# Rigid-Flex_HDMI_Switch.net
KiCad netlist of a schematic drawn in EAGLE
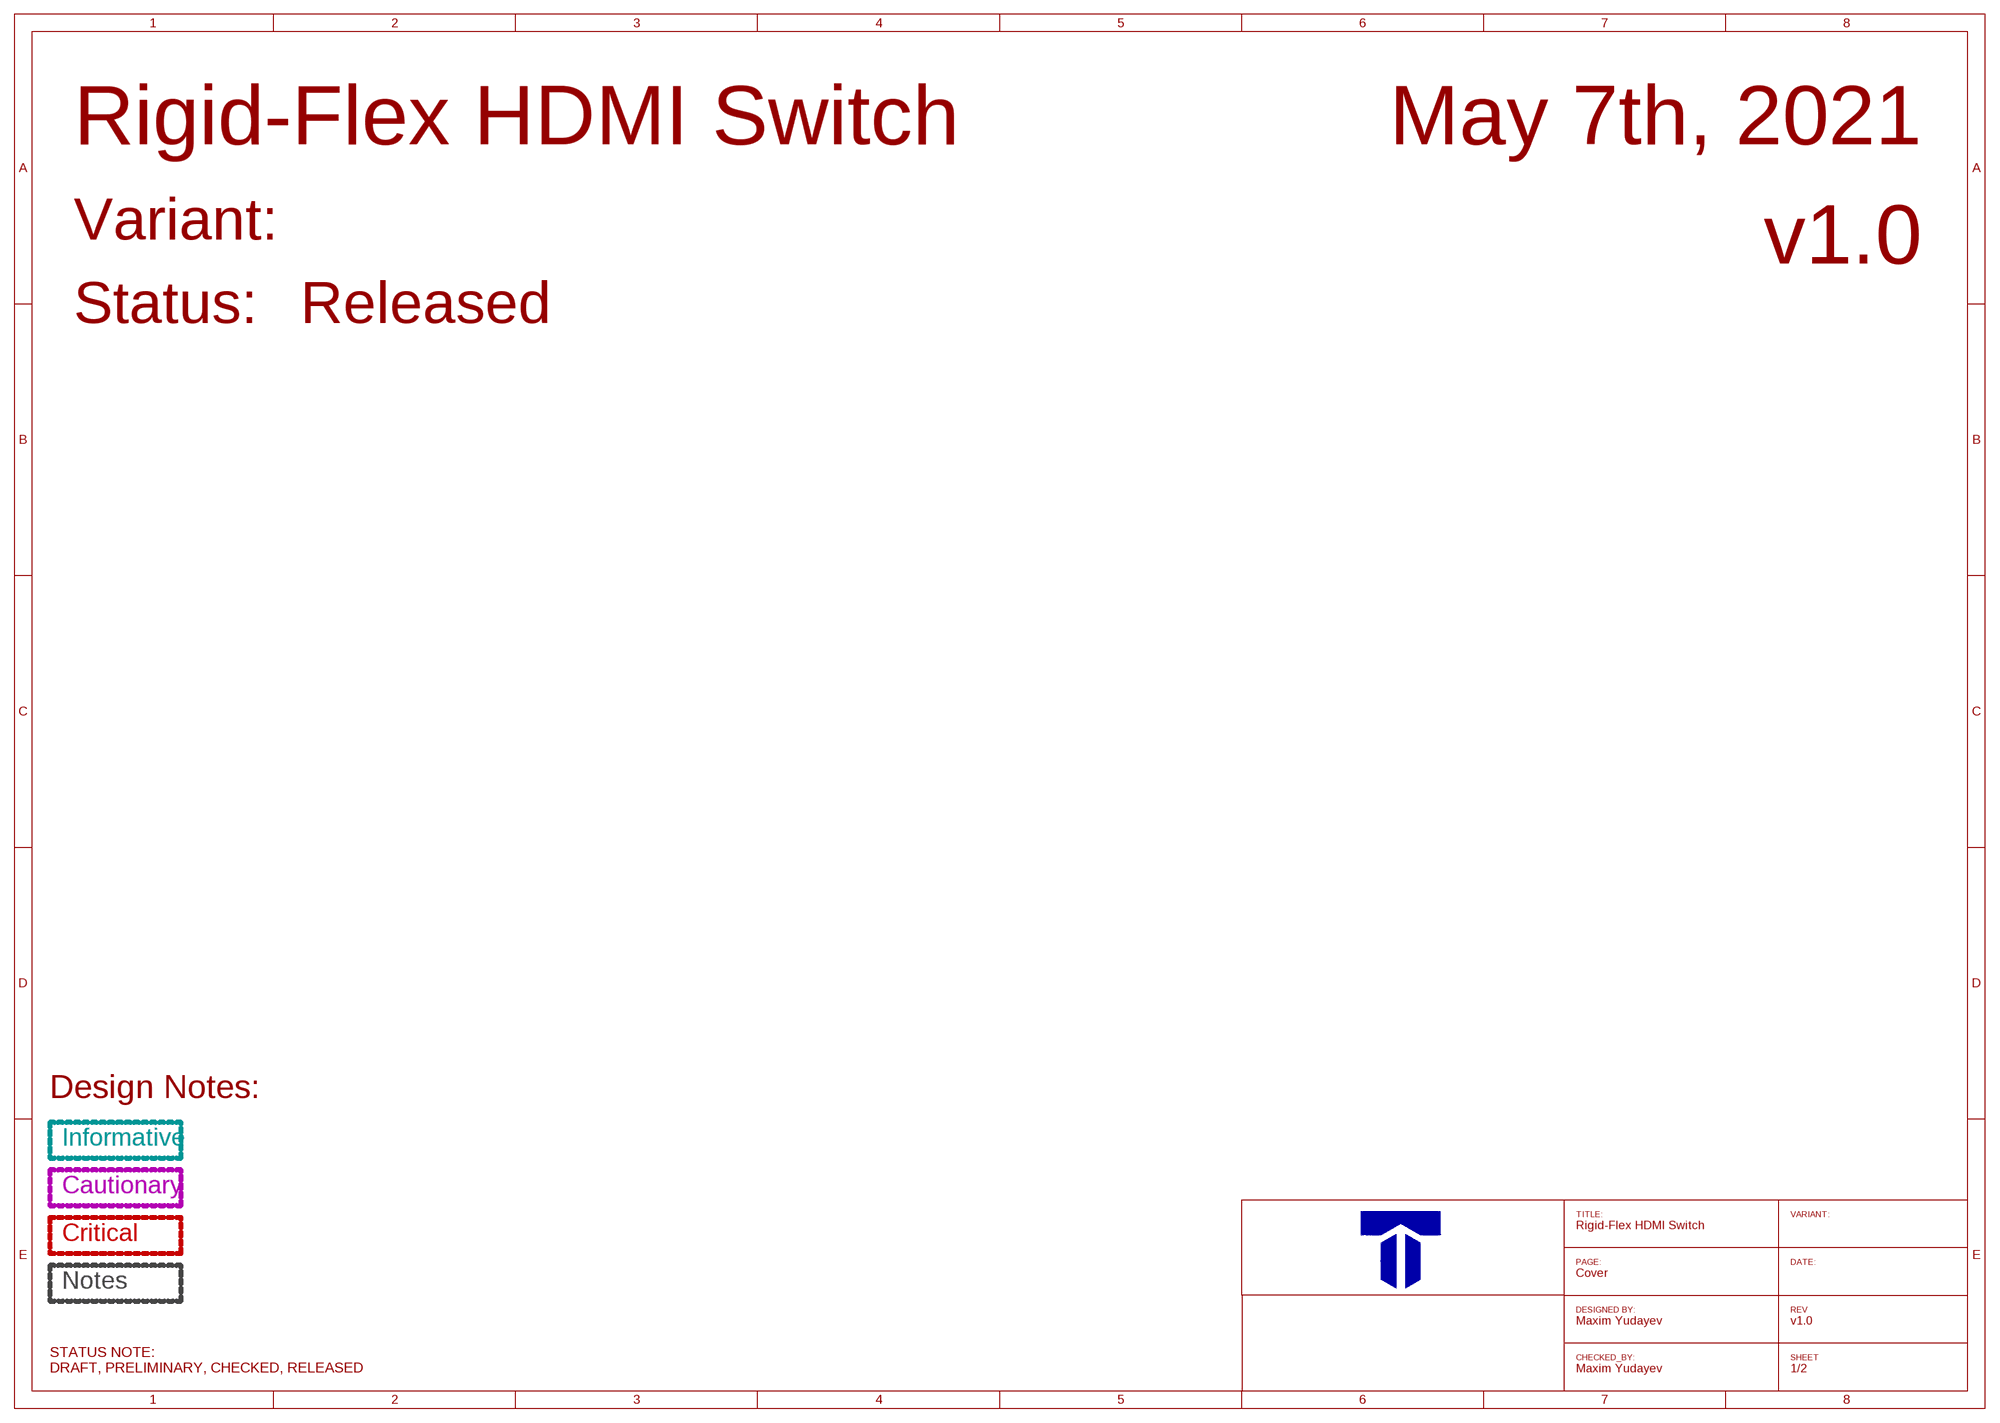
[diagram p0: schematic, sheet 1]
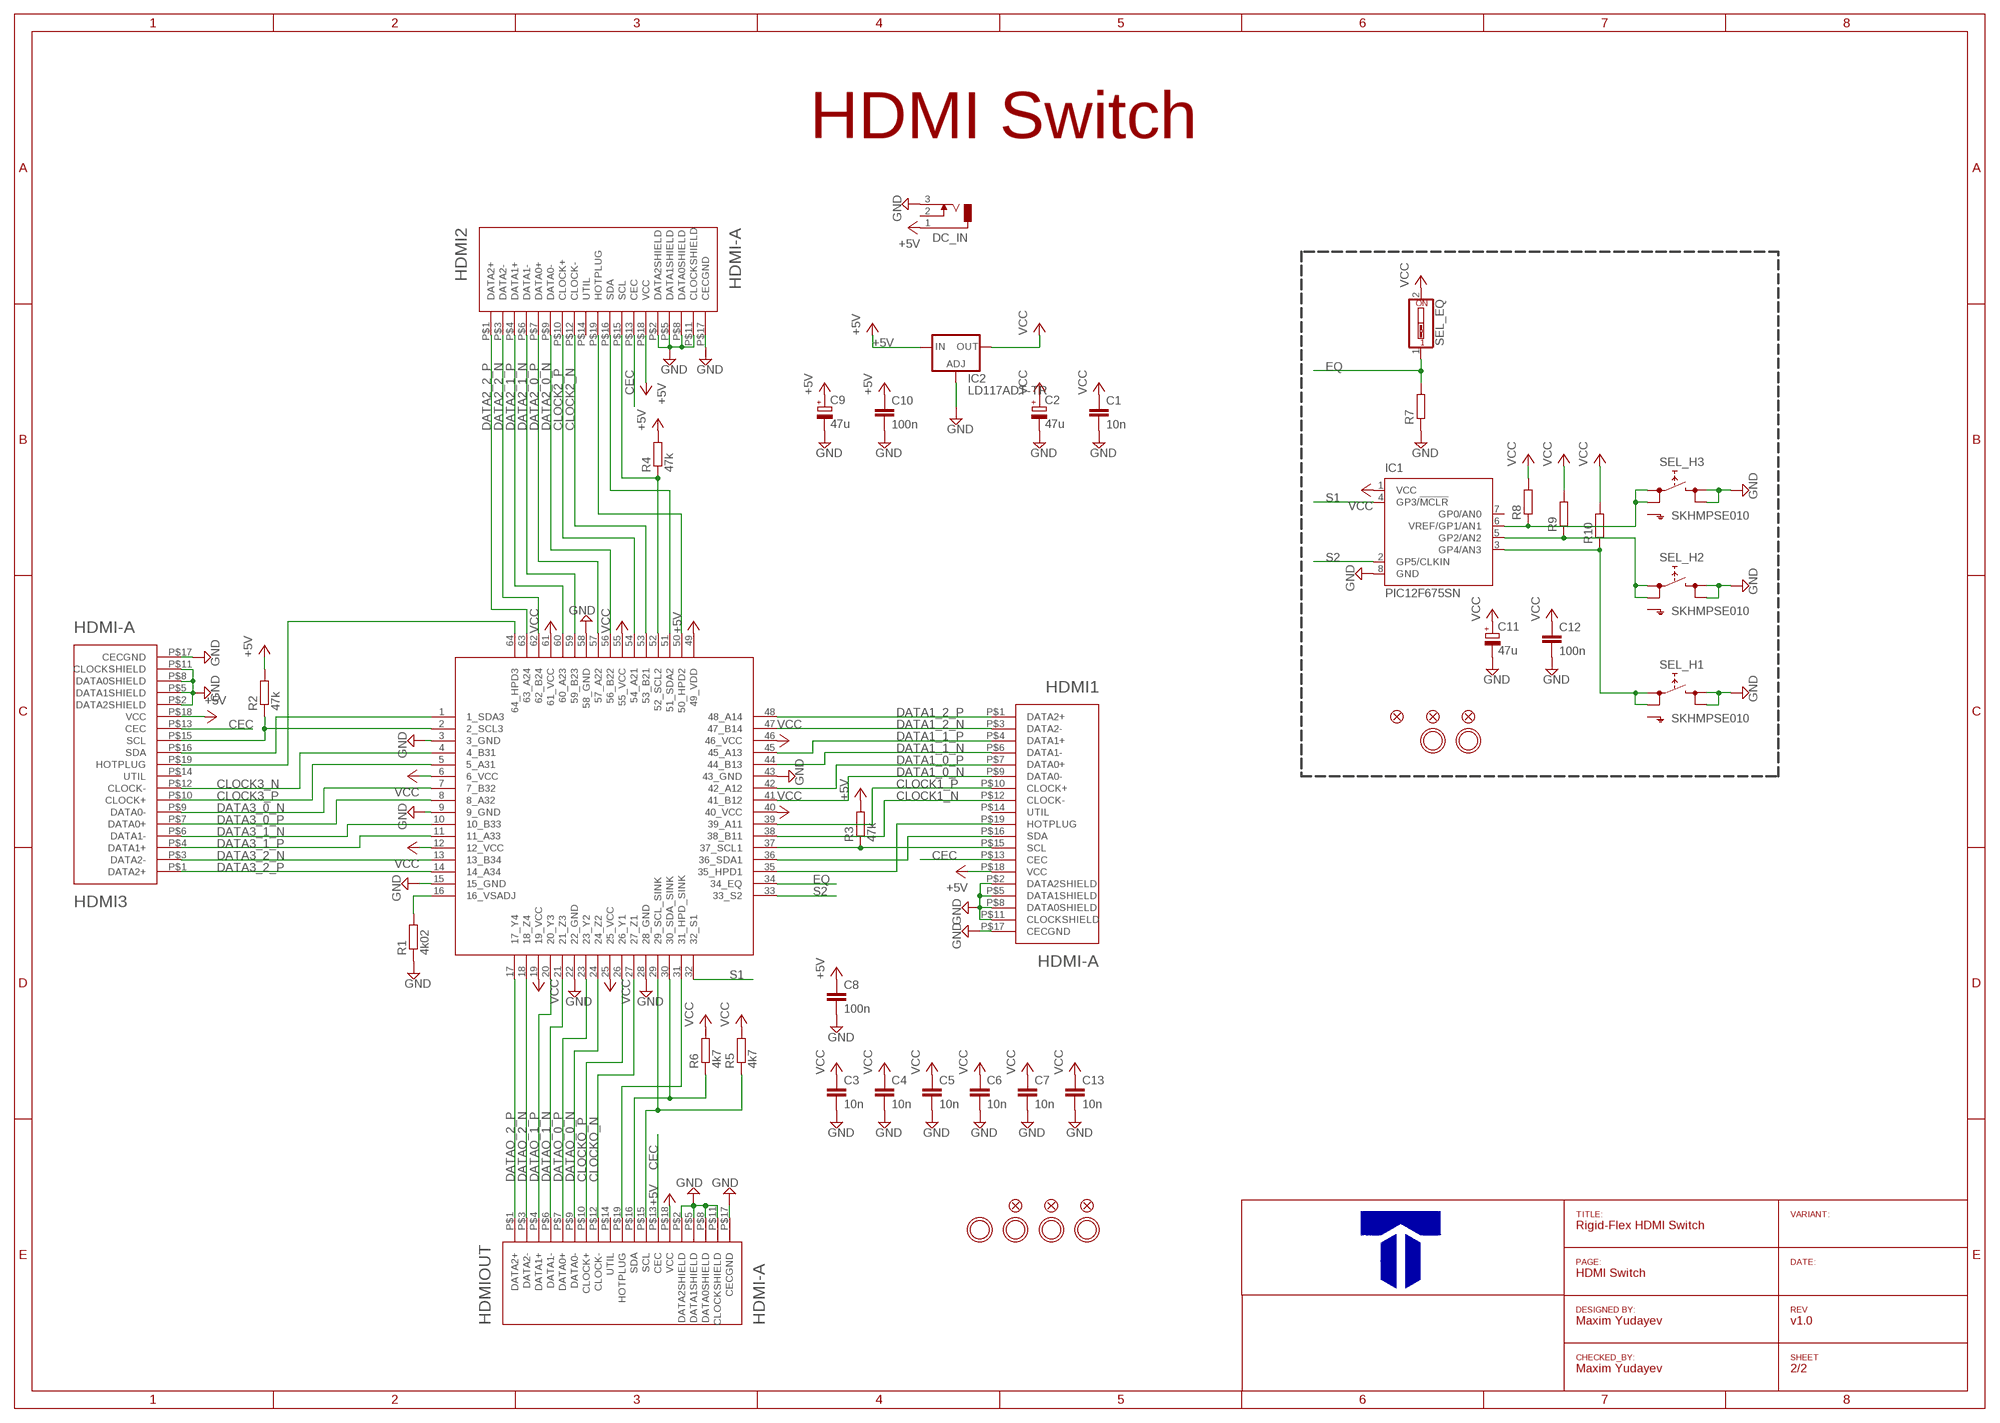
[diagram p1: schematic, sheet 2]

(export (version "E")
  (design (tool "Eeschema 10.0.6"))
  (components
    (comp (ref "C1")
      (value "10n")
      (footprint "eagle-import:C0402")
      (libsource (lib "eagle-import") (part "C-EUC0402"))
    )
    (comp (ref "C2")
      (value "47u")
      (footprint "eagle-import:SMC_A")
      (libsource (lib "eagle-import") (part "CPOL-EUSMCA"))
    )
    (comp (ref "C3")
      (value "10n")
      (footprint "eagle-import:0402")
      (libsource (lib "eagle-import") (part "C0402"))
    )
    (comp (ref "C4")
      (value "10n")
      (footprint "eagle-import:0402")
      (libsource (lib "eagle-import") (part "C0402"))
    )
    (comp (ref "C5")
      (value "10n")
      (footprint "eagle-import:0402")
      (libsource (lib "eagle-import") (part "C0402"))
    )
    (comp (ref "C6")
      (value "10n")
      (footprint "eagle-import:0402")
      (libsource (lib "eagle-import") (part "C0402"))
    )
    (comp (ref "C7")
      (value "10n")
      (footprint "eagle-import:0402")
      (libsource (lib "eagle-import") (part "C0402"))
    )
    (comp (ref "C8")
      (value "100n")
      (footprint "eagle-import:0402")
      (libsource (lib "eagle-import") (part "C0402"))
    )
    (comp (ref "C9")
      (value "47u")
      (footprint "eagle-import:SMC_A")
      (libsource (lib "eagle-import") (part "CPOL-EUSMCA"))
    )
    (comp (ref "C10")
      (value "100n")
      (footprint "eagle-import:C0402")
      (libsource (lib "eagle-import") (part "C-EUC0402"))
    )
    (comp (ref "C11")
      (value "47u")
      (footprint "eagle-import:SMC_A")
      (libsource (lib "eagle-import") (part "CPOL-EUSMCA"))
    )
    (comp (ref "C12")
      (value "100n")
      (footprint "eagle-import:C0402")
      (libsource (lib "eagle-import") (part "C-EUC0402"))
    )
    (comp (ref "C13")
      (value "10n")
      (footprint "eagle-import:0402")
      (libsource (lib "eagle-import") (part "C0402"))
    )
    (comp (ref "DC_IN")
      (value "DCJ0303")
      (footprint "eagle-import:DCJ0303")
      (libsource (lib "eagle-import") (part "DCJ0303"))
    )
    (comp (ref "FID1")
      (value "FIDUCIAL\"\"")
      (footprint "eagle-import:FIDUCIAL_1MM")
      (libsource (lib "eagle-import") (part "FIDUCIAL{dblquote}{dblquote}"))
    )
    (comp (ref "FID2")
      (value "FIDUCIAL\"\"")
      (footprint "eagle-import:FIDUCIAL_1MM")
      (libsource (lib "eagle-import") (part "FIDUCIAL{dblquote}{dblquote}"))
    )
    (comp (ref "FID3")
      (value "FIDUCIAL\"\"")
      (footprint "eagle-import:FIDUCIAL_1MM")
      (libsource (lib "eagle-import") (part "FIDUCIAL{dblquote}{dblquote}"))
    )
    (comp (ref "FID4")
      (value "FIDUCIAL\"\"")
      (footprint "eagle-import:FIDUCIAL_1MM")
      (libsource (lib "eagle-import") (part "FIDUCIAL{dblquote}{dblquote}"))
    )
    (comp (ref "FID5")
      (value "FIDUCIAL\"\"")
      (footprint "eagle-import:FIDUCIAL_1MM")
      (libsource (lib "eagle-import") (part "FIDUCIAL{dblquote}{dblquote}"))
    )
    (comp (ref "FID6")
      (value "FIDUCIAL\"\"")
      (footprint "eagle-import:FIDUCIAL_1MM")
      (libsource (lib "eagle-import") (part "FIDUCIAL{dblquote}{dblquote}"))
    )
    (comp (ref "HDMI1")
      (value "HDMI-A")
      (footprint "eagle-import:HDMI_A")
      (libsource (lib "eagle-import") (part "HDMI-A"))
    )
    (comp (ref "HDMI2")
      (value "HDMI-A")
      (footprint "eagle-import:HDMI_A")
      (libsource (lib "eagle-import") (part "HDMI-A"))
    )
    (comp (ref "HDMI3")
      (value "HDMI-A")
      (footprint "eagle-import:HDMI_A")
      (libsource (lib "eagle-import") (part "HDMI-A"))
    )
    (comp (ref "HDMIOUT")
      (value "HDMI-A")
      (footprint "eagle-import:HDMI_A")
      (libsource (lib "eagle-import") (part "HDMI-A"))
    )
    (comp (ref "IC1")
      (value "PIC12F675SN")
      (footprint "eagle-import:SO-08")
      (fields (field (name "MF") "MICROCHIP") (field (name "MPN") "PIC12F675-E/SN"))
      (libsource (lib "eagle-import") (part "PIC12F675SN"))
    )
    (comp (ref "IC2")
      (value "LD117ADT-TR")
      (footprint "eagle-import:DPACK")
      (libsource (lib "eagle-import") (part "LD117A?DT-TR"))
    )
    (comp (ref "R1")
      (value "4k02")
      (footprint "eagle-import:0402")
      (libsource (lib "eagle-import") (part "R0402"))
    )
    (comp (ref "R2")
      (value "47k")
      (footprint "eagle-import:0402")
      (libsource (lib "eagle-import") (part "R0402"))
    )
    (comp (ref "R3")
      (value "47k")
      (footprint "eagle-import:0402")
      (libsource (lib "eagle-import") (part "R0402"))
    )
    (comp (ref "R4")
      (value "47k")
      (footprint "eagle-import:0402")
      (libsource (lib "eagle-import") (part "R0402"))
    )
    (comp (ref "R5")
      (value "4k7")
      (footprint "eagle-import:0402")
      (libsource (lib "eagle-import") (part "R0402"))
    )
    (comp (ref "R6")
      (value "4k7")
      (footprint "eagle-import:0402")
      (libsource (lib "eagle-import") (part "R0402"))
    )
    (comp (ref "R7")
      (value "R-EU_R0805")
      (footprint "eagle-import:R0805")
      (libsource (lib "eagle-import") (part "R-EU_R0805"))
    )
    (comp (ref "R8")
      (value "R-EU_R0805")
      (footprint "eagle-import:R0805")
      (libsource (lib "eagle-import") (part "R-EU_R0805"))
    )
    (comp (ref "R9")
      (value "R-EU_R0805")
      (footprint "eagle-import:R0805")
      (libsource (lib "eagle-import") (part "R-EU_R0805"))
    )
    (comp (ref "R10")
      (value "R-EU_R0805")
      (footprint "eagle-import:R0805")
      (libsource (lib "eagle-import") (part "R-EU_R0805"))
    )
    (comp (ref "SEL_EQ")
      (value "SW_DIP-1")
      (footprint "eagle-import:EDG-01")
      (libsource (lib "eagle-import") (part "SW_DIP-1"))
    )
    (comp (ref "SEL_H1")
      (value "SKHMPSE010")
      (footprint "eagle-import:SKHMPXE010")
      (libsource (lib "eagle-import") (part "SKHMPE010S"))
    )
    (comp (ref "SEL_H2")
      (value "SKHMPSE010")
      (footprint "eagle-import:SKHMPXE010")
      (libsource (lib "eagle-import") (part "SKHMPE010S"))
    )
    (comp (ref "SEL_H3")
      (value "SKHMPSE010")
      (footprint "eagle-import:SKHMPXE010")
      (libsource (lib "eagle-import") (part "SKHMPE010S"))
    )
    (comp (ref "U$1")
      (value "MOUNTINGHOLE3.0")
      (footprint "eagle-import:MOUNTINGHOLE_3.0_PLATED")
      (libsource (lib "eagle-import") (part "MOUNTINGHOLE3.0"))
    )
    (comp (ref "U$2")
      (value "MOUNTINGHOLE3.0")
      (footprint "eagle-import:MOUNTINGHOLE_3.0_PLATED")
      (libsource (lib "eagle-import") (part "MOUNTINGHOLE3.0"))
    )
    (comp (ref "U$31")
      (value "MOUNTINGHOLE3.0")
      (footprint "eagle-import:MOUNTINGHOLE_3.0_PLATED")
      (libsource (lib "eagle-import") (part "MOUNTINGHOLE3.0"))
    )
    (comp (ref "U$32")
      (value "MOUNTINGHOLE3.0")
      (footprint "eagle-import:MOUNTINGHOLE_3.0_PLATED")
      (libsource (lib "eagle-import") (part "MOUNTINGHOLE3.0"))
    )
    (comp (ref "U$33")
      (value "MOUNTINGHOLE3.0")
      (footprint "eagle-import:MOUNTINGHOLE_3.0_PLATED")
      (libsource (lib "eagle-import") (part "MOUNTINGHOLE3.0"))
    )
    (comp (ref "U$34")
      (value "MOUNTINGHOLE3.0")
      (footprint "eagle-import:MOUNTINGHOLE_3.0_PLATED")
      (libsource (lib "eagle-import") (part "MOUNTINGHOLE3.0"))
    )
    (comp (ref "U1")
      (value "TMDS351TQFP64")
      (footprint "eagle-import:QFP50P1200X1200X120-64")
      (libsource (lib "eagle-import") (part "TMDS351TQFP64"))
    )
  )
  (nets
    (net (code "1") (name "+5V") (class "Default")
      (node (ref "C10") (pin "1") (pinfunction "1_1") (pintype "passive"))
      (node (ref "C8") (pin "1") (pinfunction "1_1") (pintype "passive"))
      (node (ref "C9") (pin "+") (pinfunction "+_+") (pintype "passive"))
      (node (ref "DC_IN") (pin "1") (pinfunction "1_1") (pintype "passive"))
      (node (ref "HDMI1") (pin "P$18") (pinfunction "VCC_P$18") (pintype "bidirectional"))
      (node (ref "HDMI2") (pin "P$18") (pinfunction "VCC_P$18") (pintype "bidirectional"))
      (node (ref "HDMI3") (pin "P$18") (pinfunction "VCC_P$18") (pintype "bidirectional"))
      (node (ref "HDMIOUT") (pin "P$18") (pinfunction "VCC_P$18") (pintype "bidirectional"))
      (node (ref "IC2") (pin "3") (pinfunction "IN_3") (pintype "input"))
      (node (ref "R2") (pin "2") (pinfunction "2_2") (pintype "passive"))
      (node (ref "R3") (pin "2") (pinfunction "2_2") (pintype "passive"))
      (node (ref "R4") (pin "2") (pinfunction "2_2") (pintype "passive"))
      (node (ref "U1") (pin "49") (pinfunction "49_VDD_49") (pintype "bidirectional"))
    )
    (net (code "2") (name "CEC") (class "Default")
      (node (ref "HDMI1") (pin "P$13") (pinfunction "CEC_P$13") (pintype "bidirectional"))
      (node (ref "HDMI2") (pin "P$13") (pinfunction "CEC_P$13") (pintype "bidirectional"))
      (node (ref "HDMI3") (pin "P$13") (pinfunction "CEC_P$13") (pintype "bidirectional"))
      (node (ref "HDMIOUT") (pin "P$13") (pinfunction "CEC_P$13") (pintype "bidirectional"))
    )
    (net (code "3") (name "CLOCK1_N") (class "Default")
      (node (ref "HDMI1") (pin "P$12") (pinfunction "CLOCK-_P$12") (pintype "bidirectional"))
      (node (ref "U1") (pin "38") (pinfunction "38_B11_38") (pintype "bidirectional"))
    )
    (net (code "4") (name "CLOCK1_P") (class "Default")
      (node (ref "HDMI1") (pin "P$10") (pinfunction "CLOCK+_P$10") (pintype "bidirectional"))
      (node (ref "U1") (pin "39") (pinfunction "39_A11_39") (pintype "bidirectional"))
    )
    (net (code "5") (name "CLOCK2_N") (class "Default")
      (node (ref "HDMI2") (pin "P$12") (pinfunction "CLOCK-_P$12") (pintype "bidirectional"))
      (node (ref "U1") (pin "53") (pinfunction "53_B21_53") (pintype "bidirectional"))
    )
    (net (code "6") (name "CLOCK2_P") (class "Default")
      (node (ref "HDMI2") (pin "P$10") (pinfunction "CLOCK+_P$10") (pintype "bidirectional"))
      (node (ref "U1") (pin "54") (pinfunction "54_A21_54") (pintype "bidirectional"))
    )
    (net (code "7") (name "CLOCK3_N") (class "Default")
      (node (ref "HDMI3") (pin "P$12") (pinfunction "CLOCK-_P$12") (pintype "bidirectional"))
      (node (ref "U1") (pin "4") (pinfunction "4_B31_4") (pintype "bidirectional"))
    )
    (net (code "8") (name "CLOCK3_P") (class "Default")
      (node (ref "HDMI3") (pin "P$10") (pinfunction "CLOCK+_P$10") (pintype "bidirectional"))
      (node (ref "U1") (pin "5") (pinfunction "5_A31_5") (pintype "bidirectional"))
    )
    (net (code "9") (name "CLOCKO_N") (class "Default")
      (node (ref "HDMIOUT") (pin "P$12") (pinfunction "CLOCK-_P$12") (pintype "bidirectional"))
      (node (ref "U1") (pin "27") (pinfunction "27_Z1_27") (pintype "bidirectional"))
    )
    (net (code "10") (name "CLOCKO_P") (class "Default")
      (node (ref "HDMIOUT") (pin "P$10") (pinfunction "CLOCK+_P$10") (pintype "bidirectional"))
      (node (ref "U1") (pin "26") (pinfunction "26_Y1_26") (pintype "bidirectional"))
    )
    (net (code "11") (name "DATA1_0_N") (class "Default")
      (node (ref "HDMI1") (pin "P$9") (pinfunction "DATA0-_P$9") (pintype "bidirectional"))
      (node (ref "U1") (pin "41") (pinfunction "41_B12_41") (pintype "bidirectional"))
    )
    (net (code "12") (name "DATA1_0_P") (class "Default")
      (node (ref "HDMI1") (pin "P$7") (pinfunction "DATA0+_P$7") (pintype "bidirectional"))
      (node (ref "U1") (pin "42") (pinfunction "42_A12_42") (pintype "bidirectional"))
    )
    (net (code "13") (name "DATA1_1_N") (class "Default")
      (node (ref "HDMI1") (pin "P$6") (pinfunction "DATA1-_P$6") (pintype "bidirectional"))
      (node (ref "U1") (pin "44") (pinfunction "44_B13_44") (pintype "bidirectional"))
    )
    (net (code "14") (name "DATA1_1_P") (class "Default")
      (node (ref "HDMI1") (pin "P$4") (pinfunction "DATA1+_P$4") (pintype "bidirectional"))
      (node (ref "U1") (pin "45") (pinfunction "45_A13_45") (pintype "bidirectional"))
    )
    (net (code "15") (name "DATA1_2_N") (class "Default")
      (node (ref "HDMI1") (pin "P$3") (pinfunction "DATA2-_P$3") (pintype "bidirectional"))
      (node (ref "U1") (pin "47") (pinfunction "47_B14_47") (pintype "bidirectional"))
    )
    (net (code "16") (name "DATA1_2_P") (class "Default")
      (node (ref "HDMI1") (pin "P$1") (pinfunction "DATA2+_P$1") (pintype "bidirectional"))
      (node (ref "U1") (pin "48") (pinfunction "48_A14_48") (pintype "bidirectional"))
    )
    (net (code "17") (name "DATA2_0_N") (class "Default")
      (node (ref "HDMI2") (pin "P$9") (pinfunction "DATA0-_P$9") (pintype "bidirectional"))
      (node (ref "U1") (pin "56") (pinfunction "56_B22_56") (pintype "bidirectional"))
    )
    (net (code "18") (name "DATA2_0_P") (class "Default")
      (node (ref "HDMI2") (pin "P$7") (pinfunction "DATA0+_P$7") (pintype "bidirectional"))
      (node (ref "U1") (pin "57") (pinfunction "57_A22_57") (pintype "bidirectional"))
    )
    (net (code "19") (name "DATA2_1_N") (class "Default")
      (node (ref "HDMI2") (pin "P$6") (pinfunction "DATA1-_P$6") (pintype "bidirectional"))
      (node (ref "U1") (pin "59") (pinfunction "59_B23_59") (pintype "bidirectional"))
    )
    (net (code "20") (name "DATA2_1_P") (class "Default")
      (node (ref "HDMI2") (pin "P$4") (pinfunction "DATA1+_P$4") (pintype "bidirectional"))
      (node (ref "U1") (pin "60") (pinfunction "60_A23_60") (pintype "bidirectional"))
    )
    (net (code "21") (name "DATA2_2_N") (class "Default")
      (node (ref "HDMI2") (pin "P$3") (pinfunction "DATA2-_P$3") (pintype "bidirectional"))
      (node (ref "U1") (pin "62") (pinfunction "62_B24_62") (pintype "bidirectional"))
    )
    (net (code "22") (name "DATA2_2_P") (class "Default")
      (node (ref "HDMI2") (pin "P$1") (pinfunction "DATA2+_P$1") (pintype "bidirectional"))
      (node (ref "U1") (pin "63") (pinfunction "63_A24_63") (pintype "bidirectional"))
    )
    (net (code "23") (name "DATA3_0_N") (class "Default")
      (node (ref "HDMI3") (pin "P$9") (pinfunction "DATA0-_P$9") (pintype "bidirectional"))
      (node (ref "U1") (pin "7") (pinfunction "7_B32_7") (pintype "bidirectional"))
    )
    (net (code "24") (name "DATA3_0_P") (class "Default")
      (node (ref "HDMI3") (pin "P$7") (pinfunction "DATA0+_P$7") (pintype "bidirectional"))
      (node (ref "U1") (pin "8") (pinfunction "8_A32_8") (pintype "bidirectional"))
    )
    (net (code "25") (name "DATA3_1_N") (class "Default")
      (node (ref "HDMI3") (pin "P$6") (pinfunction "DATA1-_P$6") (pintype "bidirectional"))
      (node (ref "U1") (pin "10") (pinfunction "10_B33_10") (pintype "bidirectional"))
    )
    (net (code "26") (name "DATA3_1_P") (class "Default")
      (node (ref "HDMI3") (pin "P$4") (pinfunction "DATA1+_P$4") (pintype "bidirectional"))
      (node (ref "U1") (pin "11") (pinfunction "11_A33_11") (pintype "bidirectional"))
    )
    (net (code "27") (name "DATA3_2_N") (class "Default")
      (node (ref "HDMI3") (pin "P$3") (pinfunction "DATA2-_P$3") (pintype "bidirectional"))
      (node (ref "U1") (pin "13") (pinfunction "13_B34_13") (pintype "bidirectional"))
    )
    (net (code "28") (name "DATA3_2_P") (class "Default")
      (node (ref "HDMI3") (pin "P$1") (pinfunction "DATA2+_P$1") (pintype "bidirectional"))
      (node (ref "U1") (pin "14") (pinfunction "14_A34_14") (pintype "bidirectional"))
    )
    (net (code "29") (name "DATAO_0_N") (class "Default")
      (node (ref "HDMIOUT") (pin "P$9") (pinfunction "DATA0-_P$9") (pintype "bidirectional"))
      (node (ref "U1") (pin "24") (pinfunction "24_Z2_24") (pintype "bidirectional"))
    )
    (net (code "30") (name "DATAO_0_P") (class "Default")
      (node (ref "HDMIOUT") (pin "P$7") (pinfunction "DATA0+_P$7") (pintype "bidirectional"))
      (node (ref "U1") (pin "23") (pinfunction "23_Y2_23") (pintype "bidirectional"))
    )
    (net (code "31") (name "DATAO_1_N") (class "Default")
      (node (ref "HDMIOUT") (pin "P$6") (pinfunction "DATA1-_P$6") (pintype "bidirectional"))
      (node (ref "U1") (pin "21") (pinfunction "21_Z3_21") (pintype "bidirectional"))
    )
    (net (code "32") (name "DATAO_1_P") (class "Default")
      (node (ref "HDMIOUT") (pin "P$4") (pinfunction "DATA1+_P$4") (pintype "bidirectional"))
      (node (ref "U1") (pin "20") (pinfunction "20_Y3_20") (pintype "bidirectional"))
    )
    (net (code "33") (name "DATAO_2_N") (class "Default")
      (node (ref "HDMIOUT") (pin "P$3") (pinfunction "DATA2-_P$3") (pintype "bidirectional"))
      (node (ref "U1") (pin "18") (pinfunction "18_Z4_18") (pintype "bidirectional"))
    )
    (net (code "34") (name "DATAO_2_P") (class "Default")
      (node (ref "HDMIOUT") (pin "P$1") (pinfunction "DATA2+_P$1") (pintype "bidirectional"))
      (node (ref "U1") (pin "17") (pinfunction "17_Y4_17") (pintype "bidirectional"))
    )
    (net (code "35") (name "EQ") (class "Default")
      (node (ref "R7") (pin "2") (pinfunction "2_2") (pintype "passive"))
      (node (ref "SEL_EQ") (pin "1") (pinfunction "1_1") (pintype "passive"))
      (node (ref "U1") (pin "34") (pinfunction "34_EQ_34") (pintype "bidirectional"))
    )
    (net (code "36") (name "GND") (class "Default")
      (node (ref "C1") (pin "2") (pinfunction "2_2") (pintype "passive"))
      (node (ref "C10") (pin "2") (pinfunction "2_2") (pintype "passive"))
      (node (ref "C11") (pin "-") (pinfunction "-_-") (pintype "passive"))
      (node (ref "C12") (pin "2") (pinfunction "2_2") (pintype "passive"))
      (node (ref "C13") (pin "2") (pinfunction "2_2") (pintype "passive"))
      (node (ref "C2") (pin "-") (pinfunction "-_-") (pintype "passive"))
      (node (ref "C3") (pin "2") (pinfunction "2_2") (pintype "passive"))
      (node (ref "C4") (pin "2") (pinfunction "2_2") (pintype "passive"))
      (node (ref "C5") (pin "2") (pinfunction "2_2") (pintype "passive"))
      (node (ref "C6") (pin "2") (pinfunction "2_2") (pintype "passive"))
      (node (ref "C7") (pin "2") (pinfunction "2_2") (pintype "passive"))
      (node (ref "C8") (pin "2") (pinfunction "2_2") (pintype "passive"))
      (node (ref "C9") (pin "-") (pinfunction "-_-") (pintype "passive"))
      (node (ref "DC_IN") (pin "3") (pinfunction "3_3") (pintype "passive"))
      (node (ref "HDMI1") (pin "P$11") (pinfunction "CLOCKSHIELD_P$11") (pintype "bidirectional"))
      (node (ref "HDMI1") (pin "P$17") (pinfunction "CECGND_P$17") (pintype "bidirectional"))
      (node (ref "HDMI1") (pin "P$2") (pinfunction "DATA2SHIELD_P$2") (pintype "bidirectional"))
      (node (ref "HDMI1") (pin "P$5") (pinfunction "DATA1SHIELD_P$5") (pintype "bidirectional"))
      (node (ref "HDMI1") (pin "P$8") (pinfunction "DATA0SHIELD_P$8") (pintype "bidirectional"))
      (node (ref "HDMI2") (pin "P$11") (pinfunction "CLOCKSHIELD_P$11") (pintype "bidirectional"))
      (node (ref "HDMI2") (pin "P$17") (pinfunction "CECGND_P$17") (pintype "bidirectional"))
      (node (ref "HDMI2") (pin "P$2") (pinfunction "DATA2SHIELD_P$2") (pintype "bidirectional"))
      (node (ref "HDMI2") (pin "P$5") (pinfunction "DATA1SHIELD_P$5") (pintype "bidirectional"))
      (node (ref "HDMI2") (pin "P$8") (pinfunction "DATA0SHIELD_P$8") (pintype "bidirectional"))
      (node (ref "HDMI3") (pin "P$11") (pinfunction "CLOCKSHIELD_P$11") (pintype "bidirectional"))
      (node (ref "HDMI3") (pin "P$17") (pinfunction "CECGND_P$17") (pintype "bidirectional"))
      (node (ref "HDMI3") (pin "P$2") (pinfunction "DATA2SHIELD_P$2") (pintype "bidirectional"))
      (node (ref "HDMI3") (pin "P$5") (pinfunction "DATA1SHIELD_P$5") (pintype "bidirectional"))
      (node (ref "HDMI3") (pin "P$8") (pinfunction "DATA0SHIELD_P$8") (pintype "bidirectional"))
      (node (ref "HDMIOUT") (pin "P$11") (pinfunction "CLOCKSHIELD_P$11") (pintype "bidirectional"))
      (node (ref "HDMIOUT") (pin "P$17") (pinfunction "CECGND_P$17") (pintype "bidirectional"))
      (node (ref "HDMIOUT") (pin "P$2") (pinfunction "DATA2SHIELD_P$2") (pintype "bidirectional"))
      (node (ref "HDMIOUT") (pin "P$5") (pinfunction "DATA1SHIELD_P$5") (pintype "bidirectional"))
      (node (ref "HDMIOUT") (pin "P$8") (pinfunction "DATA0SHIELD_P$8") (pintype "bidirectional"))
      (node (ref "IC1") (pin "8") (pinfunction "GND_8") (pintype "power_in"))
      (node (ref "IC2") (pin "1") (pinfunction "ADJ_1") (pintype "input"))
      (node (ref "R1") (pin "1") (pinfunction "1_1") (pintype "passive"))
      (node (ref "R7") (pin "1") (pinfunction "1_1") (pintype "passive"))
      (node (ref "SEL_H1") (pin "3") (pinfunction "2.1_3") (pintype "passive"))
      (node (ref "SEL_H1") (pin "4") (pinfunction "2.2_4") (pintype "passive"))
      (node (ref "SEL_H2") (pin "3") (pinfunction "2.1_3") (pintype "passive"))
      (node (ref "SEL_H2") (pin "4") (pinfunction "2.2_4") (pintype "passive"))
      (node (ref "SEL_H3") (pin "3") (pinfunction "2.1_3") (pintype "passive"))
      (node (ref "SEL_H3") (pin "4") (pinfunction "2.2_4") (pintype "passive"))
      (node (ref "U1") (pin "15") (pinfunction "15_GND_15") (pintype "bidirectional"))
      (node (ref "U1") (pin "22") (pinfunction "22_GND_22") (pintype "bidirectional"))
      (node (ref "U1") (pin "28") (pinfunction "28_GND_28") (pintype "bidirectional"))
      (node (ref "U1") (pin "3") (pinfunction "3_GND_3") (pintype "bidirectional"))
      (node (ref "U1") (pin "43") (pinfunction "43_GND_43") (pintype "bidirectional"))
      (node (ref "U1") (pin "58") (pinfunction "58_GND_58") (pintype "bidirectional"))
      (node (ref "U1") (pin "9") (pinfunction "9_GND_9") (pintype "bidirectional"))
    )
    (net (code "37") (name "Net-(HDMI1-HOTPLUG)") (class "Default")
      (node (ref "HDMI1") (pin "P$19") (pinfunction "HOTPLUG_P$19") (pintype "bidirectional"))
      (node (ref "U1") (pin "35") (pinfunction "35_HPD1_35") (pintype "bidirectional"))
    )
    (net (code "38") (name "Net-(HDMI1-SCL)") (class "Default")
      (node (ref "HDMI1") (pin "P$15") (pinfunction "SCL_P$15") (pintype "bidirectional"))
      (node (ref "R3") (pin "1") (pinfunction "1_1") (pintype "passive"))
      (node (ref "U1") (pin "37") (pinfunction "37_SCL1_37") (pintype "bidirectional"))
    )
    (net (code "39") (name "Net-(HDMI1-SDA)") (class "Default")
      (node (ref "HDMI1") (pin "P$16") (pinfunction "SDA_P$16") (pintype "bidirectional"))
      (node (ref "U1") (pin "36") (pinfunction "36_SDA1_36") (pintype "bidirectional"))
    )
    (net (code "40") (name "Net-(HDMI2-HOTPLUG)") (class "Default")
      (node (ref "HDMI2") (pin "P$19") (pinfunction "HOTPLUG_P$19") (pintype "bidirectional"))
      (node (ref "U1") (pin "50") (pinfunction "50_HPD2_50") (pintype "bidirectional"))
    )
    (net (code "41") (name "Net-(HDMI2-SCL)") (class "Default")
      (node (ref "HDMI2") (pin "P$15") (pinfunction "SCL_P$15") (pintype "bidirectional"))
      (node (ref "R4") (pin "1") (pinfunction "1_1") (pintype "passive"))
      (node (ref "U1") (pin "52") (pinfunction "52_SCL2_52") (pintype "bidirectional"))
    )
    (net (code "42") (name "Net-(HDMI2-SDA)") (class "Default")
      (node (ref "HDMI2") (pin "P$16") (pinfunction "SDA_P$16") (pintype "bidirectional"))
      (node (ref "U1") (pin "51") (pinfunction "51_SDA2_51") (pintype "bidirectional"))
    )
    (net (code "43") (name "Net-(HDMI3-HOTPLUG)") (class "Default")
      (node (ref "HDMI3") (pin "P$19") (pinfunction "HOTPLUG_P$19") (pintype "bidirectional"))
      (node (ref "U1") (pin "64") (pinfunction "64_HPD3_64") (pintype "bidirectional"))
    )
    (net (code "44") (name "Net-(HDMI3-SCL)") (class "Default")
      (node (ref "HDMI3") (pin "P$15") (pinfunction "SCL_P$15") (pintype "bidirectional"))
      (node (ref "R2") (pin "1") (pinfunction "1_1") (pintype "passive"))
      (node (ref "U1") (pin "2") (pinfunction "2_SCL3_2") (pintype "bidirectional"))
    )
    (net (code "45") (name "Net-(HDMI3-SDA)") (class "Default")
      (node (ref "HDMI3") (pin "P$16") (pinfunction "SDA_P$16") (pintype "bidirectional"))
      (node (ref "U1") (pin "1") (pinfunction "1_SDA3_1") (pintype "bidirectional"))
    )
    (net (code "46") (name "Net-(HDMIOUT-HOTPLUG)") (class "Default")
      (node (ref "HDMIOUT") (pin "P$19") (pinfunction "HOTPLUG_P$19") (pintype "bidirectional"))
      (node (ref "U1") (pin "31") (pinfunction "31_HPD_SINK_31") (pintype "bidirectional"))
    )
    (net (code "47") (name "Net-(HDMIOUT-SCL)") (class "Default")
      (node (ref "HDMIOUT") (pin "P$15") (pinfunction "SCL_P$15") (pintype "bidirectional"))
      (node (ref "R5") (pin "1") (pinfunction "1_1") (pintype "passive"))
      (node (ref "U1") (pin "29") (pinfunction "29_SCL_SINK_29") (pintype "bidirectional"))
    )
    (net (code "48") (name "Net-(HDMIOUT-SDA)") (class "Default")
      (node (ref "HDMIOUT") (pin "P$16") (pinfunction "SDA_P$16") (pintype "bidirectional"))
      (node (ref "R6") (pin "1") (pinfunction "1_1") (pintype "passive"))
      (node (ref "U1") (pin "30") (pinfunction "30_SDA_SINK_30") (pintype "bidirectional"))
    )
    (net (code "49") (name "Net-(IC1-GP2{slash}AN2)") (class "Default")
      (node (ref "IC1") (pin "5") (pinfunction "GP2/AN2_5") (pintype "bidirectional"))
      (node (ref "R9") (pin "1") (pinfunction "1_1") (pintype "passive"))
      (node (ref "SEL_H2") (pin "1") (pinfunction "1.1_1") (pintype "passive"))
      (node (ref "SEL_H2") (pin "2") (pinfunction "1.2_2") (pintype "passive"))
    )
    (net (code "50") (name "Net-(IC1-GP4{slash}AN3)") (class "Default")
      (node (ref "IC1") (pin "3") (pinfunction "GP4/AN3_3") (pintype "bidirectional"))
      (node (ref "R10") (pin "1") (pinfunction "1_1") (pintype "passive"))
      (node (ref "SEL_H1") (pin "1") (pinfunction "1.1_1") (pintype "passive"))
      (node (ref "SEL_H1") (pin "2") (pinfunction "1.2_2") (pintype "passive"))
    )
    (net (code "51") (name "Net-(IC1-VREF{slash}GP1{slash}AN1)") (class "Default")
      (node (ref "IC1") (pin "6") (pinfunction "VREF/GP1/AN1_6") (pintype "bidirectional"))
      (node (ref "R8") (pin "1") (pinfunction "1_1") (pintype "passive"))
      (node (ref "SEL_H3") (pin "1") (pinfunction "1.1_1") (pintype "passive"))
      (node (ref "SEL_H3") (pin "2") (pinfunction "1.2_2") (pintype "passive"))
    )
    (net (code "52") (name "Net-(U1-16_VSADJ)") (class "Default")
      (node (ref "R1") (pin "2") (pinfunction "2_2") (pintype "passive"))
      (node (ref "U1") (pin "16") (pinfunction "16_VSADJ_16") (pintype "bidirectional"))
    )
    (net (code "53") (name "S1") (class "Default")
      (node (ref "IC1") (pin "4") (pinfunction "GP3/~{MCLR}_4") (pintype "input"))
      (node (ref "U1") (pin "32") (pinfunction "32_S1_32") (pintype "bidirectional"))
    )
    (net (code "54") (name "S2") (class "Default")
      (node (ref "IC1") (pin "2") (pinfunction "GP5/CLKIN_2") (pintype "bidirectional"))
      (node (ref "U1") (pin "33") (pinfunction "33_S2_33") (pintype "bidirectional"))
    )
    (net (code "55") (name "VCC") (class "Default")
      (node (ref "C1") (pin "1") (pinfunction "1_1") (pintype "passive"))
      (node (ref "C11") (pin "+") (pinfunction "+_+") (pintype "passive"))
      (node (ref "C12") (pin "1") (pinfunction "1_1") (pintype "passive"))
      (node (ref "C13") (pin "1") (pinfunction "1_1") (pintype "passive"))
      (node (ref "C2") (pin "+") (pinfunction "+_+") (pintype "passive"))
      (node (ref "C3") (pin "1") (pinfunction "1_1") (pintype "passive"))
      (node (ref "C4") (pin "1") (pinfunction "1_1") (pintype "passive"))
      (node (ref "C5") (pin "1") (pinfunction "1_1") (pintype "passive"))
      (node (ref "C6") (pin "1") (pinfunction "1_1") (pintype "passive"))
      (node (ref "C7") (pin "1") (pinfunction "1_1") (pintype "passive"))
      (node (ref "IC1") (pin "1") (pinfunction "VCC_1") (pintype "power_in"))
      (node (ref "IC2") (pin "4") (pinfunction "OUT_4") (pintype "passive"))
      (node (ref "R10") (pin "2") (pinfunction "2_2") (pintype "passive"))
      (node (ref "R5") (pin "2") (pinfunction "2_2") (pintype "passive"))
      (node (ref "R6") (pin "2") (pinfunction "2_2") (pintype "passive"))
      (node (ref "R8") (pin "2") (pinfunction "2_2") (pintype "passive"))
      (node (ref "R9") (pin "2") (pinfunction "2_2") (pintype "passive"))
      (node (ref "SEL_EQ") (pin "2") (pinfunction "2_2") (pintype "passive"))
      (node (ref "U1") (pin "12") (pinfunction "12_VCC_12") (pintype "bidirectional"))
      (node (ref "U1") (pin "19") (pinfunction "19_VCC_19") (pintype "bidirectional"))
      (node (ref "U1") (pin "25") (pinfunction "25_VCC_25") (pintype "bidirectional"))
      (node (ref "U1") (pin "40") (pinfunction "40_VCC_40") (pintype "bidirectional"))
      (node (ref "U1") (pin "46") (pinfunction "46_VCC_46") (pintype "bidirectional"))
      (node (ref "U1") (pin "55") (pinfunction "55_VCC_55") (pintype "bidirectional"))
      (node (ref "U1") (pin "6") (pinfunction "6_VCC_6") (pintype "bidirectional"))
      (node (ref "U1") (pin "61") (pinfunction "61_VCC_61") (pintype "bidirectional"))
    )
    (net (code "56") (name "unconnected-(DC_IN-Pad2)") (class "Default")
      (node (ref "DC_IN") (pin "2") (pinfunction "2_2") (pintype "passive"))
    )
    (net (code "57") (name "unconnected-(HDMI1-UTIL-PadP$14)") (class "Default")
      (node (ref "HDMI1") (pin "P$14") (pinfunction "UTIL_P$14") (pintype "bidirectional"))
    )
    (net (code "58") (name "unconnected-(HDMI2-UTIL-PadP$14)") (class "Default")
      (node (ref "HDMI2") (pin "P$14") (pinfunction "UTIL_P$14") (pintype "bidirectional"))
    )
    (net (code "59") (name "unconnected-(HDMI3-UTIL-PadP$14)") (class "Default")
      (node (ref "HDMI3") (pin "P$14") (pinfunction "UTIL_P$14") (pintype "bidirectional"))
    )
    (net (code "60") (name "unconnected-(HDMIOUT-UTIL-PadP$14)") (class "Default")
      (node (ref "HDMIOUT") (pin "P$14") (pinfunction "UTIL_P$14") (pintype "bidirectional"))
    )
    (net (code "61") (name "unconnected-(IC1-GP0{slash}AN0-Pad7)") (class "Default")
      (node (ref "IC1") (pin "7") (pinfunction "GP0/AN0_7") (pintype "bidirectional"))
    )
    (net (code "62") (name "unconnected-(SEL_H1-SH-Pad5)") (class "Default")
      (node (ref "SEL_H1") (pin "5") (pinfunction "SH_5") (pintype "passive"))
    )
    (net (code "63") (name "unconnected-(SEL_H2-SH-Pad5)") (class "Default")
      (node (ref "SEL_H2") (pin "5") (pinfunction "SH_5") (pintype "passive"))
    )
    (net (code "64") (name "unconnected-(SEL_H3-SH-Pad5)") (class "Default")
      (node (ref "SEL_H3") (pin "5") (pinfunction "SH_5") (pintype "passive"))
    )
  )
)
